# ZYNQ400-EMIO.net
KiCad netlist of a schematic drawn in Altium Designer
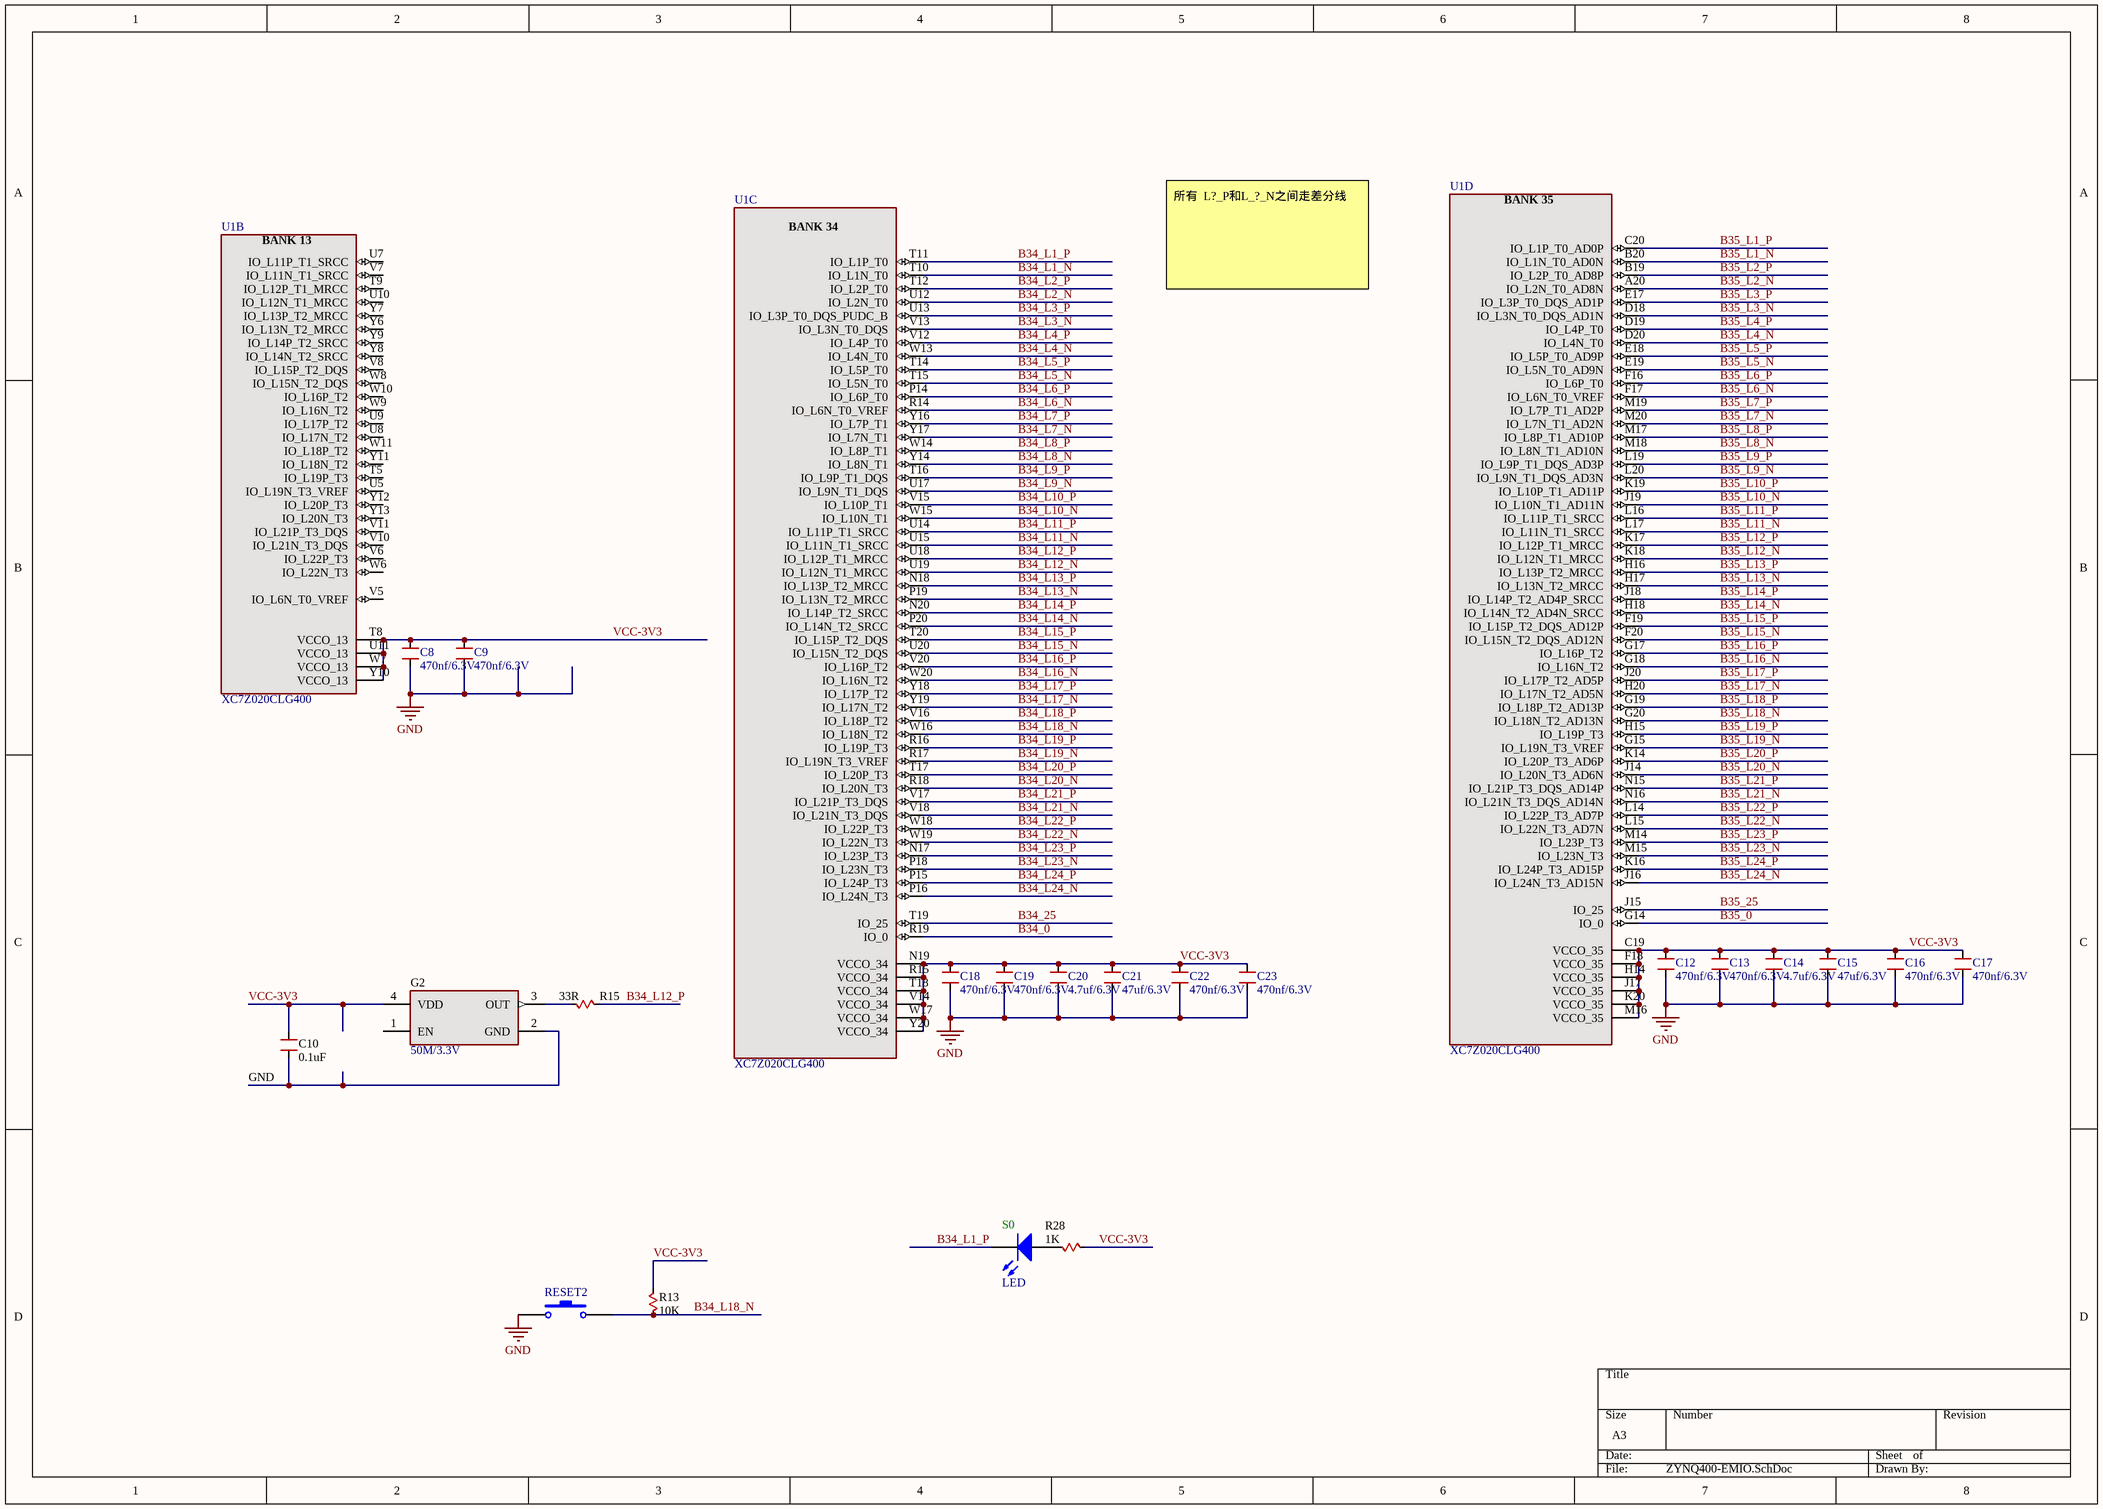
[diagram p0: ZYNQ400-EMIO.SchDoc]

(export (version "E")
  (design (tool "Eeschema 10.0.6"))
  (components
    (comp (ref "C8")
      (value "470nf/6.3V")
      (footprint "0402")
      (description "Generic Capacitor")
      (libsource (lib "Digilent") (part "CAPACITOR"))
    )
    (comp (ref "C9")
      (value "470nf/6.3V")
      (footprint "0402")
      (description "Generic Capacitor")
      (libsource (lib "Digilent") (part "CAPACITOR"))
    )
    (comp (ref "C10")
      (value "0.1uF")
      (footprint "0402")
      (description "Generic Capacitor")
      (fields (field (name "Comment") "0.1UF"))
      (libsource (lib "Digilent") (part "CAPACITOR"))
    )
    (comp (ref "C12")
      (value "470nf/6.3V")
      (footprint "0402")
      (description "Generic Capacitor")
      (libsource (lib "Digilent") (part "CAPACITOR"))
    )
    (comp (ref "C13")
      (value "470nf/6.3V")
      (footprint "0402")
      (description "Generic Capacitor")
      (libsource (lib "Digilent") (part "CAPACITOR"))
    )
    (comp (ref "C14")
      (value "4.7uf/6.3V")
      (footprint "0402")
      (description "Generic Capacitor")
      (libsource (lib "Digilent") (part "CAPACITOR"))
    )
    (comp (ref "C15")
      (value "47uf/6.3V")
      (footprint "0402")
      (description "Generic Capacitor")
      (libsource (lib "Digilent") (part "CAPACITOR"))
    )
    (comp (ref "C16")
      (value "470nf/6.3V")
      (footprint "0402")
      (description "Generic Capacitor")
      (libsource (lib "Digilent") (part "CAPACITOR"))
    )
    (comp (ref "C17")
      (value "470nf/6.3V")
      (footprint "0402")
      (description "Generic Capacitor")
      (libsource (lib "Digilent") (part "CAPACITOR"))
    )
    (comp (ref "C18")
      (value "470nf/6.3V")
      (footprint "0402")
      (description "Generic Capacitor")
      (libsource (lib "Digilent") (part "CAPACITOR"))
    )
    (comp (ref "C19")
      (value "470nf/6.3V")
      (footprint "0402")
      (description "Generic Capacitor")
      (libsource (lib "Digilent") (part "CAPACITOR"))
    )
    (comp (ref "C20")
      (value "4.7uf/6.3V")
      (footprint "0402")
      (description "Generic Capacitor")
      (libsource (lib "Digilent") (part "CAPACITOR"))
    )
    (comp (ref "C21")
      (value "47uf/6.3V")
      (footprint "0402")
      (description "Generic Capacitor")
      (libsource (lib "Digilent") (part "CAPACITOR"))
    )
    (comp (ref "C22")
      (value "470nf/6.3V")
      (footprint "0402")
      (description "Generic Capacitor")
      (libsource (lib "Digilent") (part "CAPACITOR"))
    )
    (comp (ref "C23")
      (value "470nf/6.3V")
      (footprint "0402")
      (description "Generic Capacitor")
      (libsource (lib "Digilent") (part "CAPACITOR"))
    )
    (comp (ref "G2")
      (value "50M/3.3V")
      (footprint "3.2*2.5")
      (description "3.3V HCMOS Oscillator")
      (fields (field (name "MANUFACTURER") "Fox Electronics"))
      (libsource (lib "Digilent") (part "FXO-HC5"))
    )
    (comp (ref "R13")
      (value "10K")
      (footprint "0402")
      (description "Generic Resistor")
      (libsource (lib "Digilent") (part "RESISTOR"))
    )
    (comp (ref "R15")
      (value "33R")
      (footprint "0402")
      (description "Generic Resistor")
      (libsource (lib "Digilent") (part "RESISTOR"))
    )
    (comp (ref "R28")
      (value "1K")
      (footprint "0402")
      (description "Generic Resistor")
      (libsource (lib "Digilent") (part "RESISTOR"))
    )
    (comp (ref "RESET2")
      (value "SW-PB")
      (footprint "micro button_2_SMD")
      (description "Switch")
      (fields (field (name "PUBLISHER") "Altium Limited"))
      (libsource (lib "M4(3333)") (part "SW-PB"))
    )
    (comp (ref "S0")
      (value "LED")
      (footprint "D0402")
      (description "Typical INFRARED GaAs LED")
      (fields (field (name "PUBLISHER") "Altium Limited"))
      (libsource (lib "Miscellaneous Devices") (part "LED0"))
    )
    (comp (ref "U1")
      (value "XC7Z020CLG400")
      (footprint "CLG400")
      (description "Zynq 7000 FPGA 20 Die, in a CSG 484 Package")
      (fields (field (name "MANUFACTURER") "Xilinx"))
      (libsource (lib "gjws") (part "XC7Z020-CLG400"))
    )
  )
  (nets
    (net (code "1") (name "/B34_0") (class "Default")
      (node (ref "U1") (pin "R19") (pinfunction "IO_0_R19") (pintype "bidirectional"))
    )
    (net (code "2") (name "/B34_25") (class "Default")
      (node (ref "U1") (pin "T19") (pinfunction "IO_25_T19") (pintype "bidirectional"))
    )
    (net (code "3") (name "/B34_L1_N") (class "Default")
      (node (ref "U1") (pin "T10") (pinfunction "IO_L1N_T0_T10") (pintype "bidirectional"))
    )
    (net (code "4") (name "/B34_L1_P") (class "Default")
      (node (ref "S0") (pin "2") (pinfunction "K_2") (pintype "passive"))
      (node (ref "U1") (pin "T11") (pinfunction "IO_L1P_T0_T11") (pintype "bidirectional"))
    )
    (net (code "5") (name "/B34_L2_N") (class "Default")
      (node (ref "U1") (pin "U12") (pinfunction "IO_L2N_T0_U12") (pintype "bidirectional"))
    )
    (net (code "6") (name "/B34_L2_P") (class "Default")
      (node (ref "U1") (pin "T12") (pinfunction "IO_L2P_T0_T12") (pintype "bidirectional"))
    )
    (net (code "7") (name "/B34_L3_N") (class "Default")
      (node (ref "U1") (pin "V13") (pinfunction "IO_L3N_T0_DQS_V13") (pintype "bidirectional"))
    )
    (net (code "8") (name "/B34_L3_P") (class "Default")
      (node (ref "U1") (pin "U13") (pinfunction "IO_L3P_T0_DQS_PUDC_B_U13") (pintype "bidirectional"))
    )
    (net (code "9") (name "/B34_L4_N") (class "Default")
      (node (ref "U1") (pin "W13") (pinfunction "IO_L4N_T0_W13") (pintype "bidirectional"))
    )
    (net (code "10") (name "/B34_L4_P") (class "Default")
      (node (ref "U1") (pin "V12") (pinfunction "IO_L4P_T0_V12") (pintype "bidirectional"))
    )
    (net (code "11") (name "/B34_L5_N") (class "Default")
      (node (ref "U1") (pin "T15") (pinfunction "IO_L5N_T0_T15") (pintype "bidirectional"))
    )
    (net (code "12") (name "/B34_L5_P") (class "Default")
      (node (ref "U1") (pin "T14") (pinfunction "IO_L5P_T0_T14") (pintype "bidirectional"))
    )
    (net (code "13") (name "/B34_L6_N") (class "Default")
      (node (ref "U1") (pin "R14") (pinfunction "IO_L6N_T0_VREF_R14") (pintype "bidirectional"))
    )
    (net (code "14") (name "/B34_L6_P") (class "Default")
      (node (ref "U1") (pin "P14") (pinfunction "IO_L6P_T0_P14") (pintype "bidirectional"))
    )
    (net (code "15") (name "/B34_L7_N") (class "Default")
      (node (ref "U1") (pin "Y17") (pinfunction "IO_L7N_T1_Y17") (pintype "bidirectional"))
    )
    (net (code "16") (name "/B34_L7_P") (class "Default")
      (node (ref "U1") (pin "Y16") (pinfunction "IO_L7P_T1_Y16") (pintype "bidirectional"))
    )
    (net (code "17") (name "/B34_L8_N") (class "Default")
      (node (ref "U1") (pin "Y14") (pinfunction "IO_L8N_T1_Y14") (pintype "bidirectional"))
    )
    (net (code "18") (name "/B34_L8_P") (class "Default")
      (node (ref "U1") (pin "W14") (pinfunction "IO_L8P_T1_W14") (pintype "bidirectional"))
    )
    (net (code "19") (name "/B34_L9_N") (class "Default")
      (node (ref "U1") (pin "U17") (pinfunction "IO_L9N_T1_DQS_U17") (pintype "bidirectional"))
    )
    (net (code "20") (name "/B34_L9_P") (class "Default")
      (node (ref "U1") (pin "T16") (pinfunction "IO_L9P_T1_DQS_T16") (pintype "bidirectional"))
    )
    (net (code "21") (name "/B34_L10_N") (class "Default")
      (node (ref "U1") (pin "W15") (pinfunction "IO_L10N_T1_W15") (pintype "bidirectional"))
    )
    (net (code "22") (name "/B34_L10_P") (class "Default")
      (node (ref "U1") (pin "V15") (pinfunction "IO_L10P_T1_V15") (pintype "bidirectional"))
    )
    (net (code "23") (name "/B34_L11_N") (class "Default")
      (node (ref "U1") (pin "U15") (pinfunction "IO_L11N_T1_SRCC_U15") (pintype "bidirectional"))
    )
    (net (code "24") (name "/B34_L11_P") (class "Default")
      (node (ref "U1") (pin "U14") (pinfunction "IO_L11P_T1_SRCC_U14") (pintype "bidirectional"))
    )
    (net (code "25") (name "/B34_L12_N") (class "Default")
      (node (ref "U1") (pin "U19") (pinfunction "IO_L12N_T1_MRCC_U19") (pintype "bidirectional"))
    )
    (net (code "26") (name "/B34_L12_P") (class "Default")
      (node (ref "R15") (pin "2") (pinfunction "2_2") (pintype "passive"))
      (node (ref "U1") (pin "U18") (pinfunction "IO_L12P_T1_MRCC_U18") (pintype "bidirectional"))
    )
    (net (code "27") (name "/B34_L13_N") (class "Default")
      (node (ref "U1") (pin "P19") (pinfunction "IO_L13N_T2_MRCC_P19") (pintype "bidirectional"))
    )
    (net (code "28") (name "/B34_L13_P") (class "Default")
      (node (ref "U1") (pin "N18") (pinfunction "IO_L13P_T2_MRCC_N18") (pintype "bidirectional"))
    )
    (net (code "29") (name "/B34_L14_N") (class "Default")
      (node (ref "U1") (pin "P20") (pinfunction "IO_L14N_T2_SRCC_P20") (pintype "bidirectional"))
    )
    (net (code "30") (name "/B34_L14_P") (class "Default")
      (node (ref "U1") (pin "N20") (pinfunction "IO_L14P_T2_SRCC_N20") (pintype "bidirectional"))
    )
    (net (code "31") (name "/B34_L15_N") (class "Default")
      (node (ref "U1") (pin "U20") (pinfunction "IO_L15N_T2_DQS_U20") (pintype "bidirectional"))
    )
    (net (code "32") (name "/B34_L15_P") (class "Default")
      (node (ref "U1") (pin "T20") (pinfunction "IO_L15P_T2_DQS_T20") (pintype "bidirectional"))
    )
    (net (code "33") (name "/B34_L16_N") (class "Default")
      (node (ref "U1") (pin "W20") (pinfunction "IO_L16N_T2_W20") (pintype "bidirectional"))
    )
    (net (code "34") (name "/B34_L16_P") (class "Default")
      (node (ref "U1") (pin "V20") (pinfunction "IO_L16P_T2_V20") (pintype "bidirectional"))
    )
    (net (code "35") (name "/B34_L17_N") (class "Default")
      (node (ref "U1") (pin "Y19") (pinfunction "IO_L17N_T2_Y19") (pintype "bidirectional"))
    )
    (net (code "36") (name "/B34_L17_P") (class "Default")
      (node (ref "U1") (pin "Y18") (pinfunction "IO_L17P_T2_Y18") (pintype "bidirectional"))
    )
    (net (code "37") (name "/B34_L18_N") (class "Default")
      (node (ref "R13") (pin "1") (pinfunction "1_1") (pintype "passive"))
      (node (ref "RESET2") (pin "2") (pinfunction "2_2") (pintype "passive"))
      (node (ref "U1") (pin "W16") (pinfunction "IO_L18N_T2_W16") (pintype "bidirectional"))
    )
    (net (code "38") (name "/B34_L18_P") (class "Default")
      (node (ref "U1") (pin "V16") (pinfunction "IO_L18P_T2_V16") (pintype "bidirectional"))
    )
    (net (code "39") (name "/B34_L19_N") (class "Default")
      (node (ref "U1") (pin "R17") (pinfunction "IO_L19N_T3_VREF_R17") (pintype "bidirectional"))
    )
    (net (code "40") (name "/B34_L19_P") (class "Default")
      (node (ref "U1") (pin "R16") (pinfunction "IO_L19P_T3_R16") (pintype "bidirectional"))
    )
    (net (code "41") (name "/B34_L20_N") (class "Default")
      (node (ref "U1") (pin "R18") (pinfunction "IO_L20N_T3_R18") (pintype "bidirectional"))
    )
    (net (code "42") (name "/B34_L20_P") (class "Default")
      (node (ref "U1") (pin "T17") (pinfunction "IO_L20P_T3_T17") (pintype "bidirectional"))
    )
    (net (code "43") (name "/B34_L21_N") (class "Default")
      (node (ref "U1") (pin "V18") (pinfunction "IO_L21N_T3_DQS_V18") (pintype "bidirectional"))
    )
    (net (code "44") (name "/B34_L21_P") (class "Default")
      (node (ref "U1") (pin "V17") (pinfunction "IO_L21P_T3_DQS_V17") (pintype "bidirectional"))
    )
    (net (code "45") (name "/B34_L22_N") (class "Default")
      (node (ref "U1") (pin "W19") (pinfunction "IO_L22N_T3_W19") (pintype "bidirectional"))
    )
    (net (code "46") (name "/B34_L22_P") (class "Default")
      (node (ref "U1") (pin "W18") (pinfunction "IO_L22P_T3_W18") (pintype "bidirectional"))
    )
    (net (code "47") (name "/B34_L23_N") (class "Default")
      (node (ref "U1") (pin "P18") (pinfunction "IO_L23N_T3_P18") (pintype "bidirectional"))
    )
    (net (code "48") (name "/B34_L23_P") (class "Default")
      (node (ref "U1") (pin "N17") (pinfunction "IO_L23P_T3_N17") (pintype "bidirectional"))
    )
    (net (code "49") (name "/B34_L24_N") (class "Default")
      (node (ref "U1") (pin "P16") (pinfunction "IO_L24N_T3_P16") (pintype "bidirectional"))
    )
    (net (code "50") (name "/B34_L24_P") (class "Default")
      (node (ref "U1") (pin "P15") (pinfunction "IO_L24P_T3_P15") (pintype "bidirectional"))
    )
    (net (code "51") (name "/B35_0") (class "Default")
      (node (ref "U1") (pin "G14") (pinfunction "IO_0_G14") (pintype "bidirectional"))
    )
    (net (code "52") (name "/B35_25") (class "Default")
      (node (ref "U1") (pin "J15") (pinfunction "IO_25_J15") (pintype "bidirectional"))
    )
    (net (code "53") (name "/B35_L1_N") (class "Default")
      (node (ref "U1") (pin "B20") (pinfunction "IO_L1N_T0_AD0N_B20") (pintype "bidirectional"))
    )
    (net (code "54") (name "/B35_L1_P") (class "Default")
      (node (ref "U1") (pin "C20") (pinfunction "IO_L1P_T0_AD0P_C20") (pintype "bidirectional"))
    )
    (net (code "55") (name "/B35_L2_N") (class "Default")
      (node (ref "U1") (pin "A20") (pinfunction "IO_L2N_T0_AD8N_A20") (pintype "bidirectional"))
    )
    (net (code "56") (name "/B35_L2_P") (class "Default")
      (node (ref "U1") (pin "B19") (pinfunction "IO_L2P_T0_AD8P_B19") (pintype "bidirectional"))
    )
    (net (code "57") (name "/B35_L3_N") (class "Default")
      (node (ref "U1") (pin "D18") (pinfunction "IO_L3N_T0_DQS_AD1N_D18") (pintype "bidirectional"))
    )
    (net (code "58") (name "/B35_L3_P") (class "Default")
      (node (ref "U1") (pin "E17") (pinfunction "IO_L3P_T0_DQS_AD1P_E17") (pintype "bidirectional"))
    )
    (net (code "59") (name "/B35_L4_N") (class "Default")
      (node (ref "U1") (pin "D20") (pinfunction "IO_L4N_T0_D20") (pintype "bidirectional"))
    )
    (net (code "60") (name "/B35_L4_P") (class "Default")
      (node (ref "U1") (pin "D19") (pinfunction "IO_L4P_T0_D19") (pintype "bidirectional"))
    )
    (net (code "61") (name "/B35_L5_N") (class "Default")
      (node (ref "U1") (pin "E19") (pinfunction "IO_L5N_T0_AD9N_E19") (pintype "bidirectional"))
    )
    (net (code "62") (name "/B35_L5_P") (class "Default")
      (node (ref "U1") (pin "E18") (pinfunction "IO_L5P_T0_AD9P_E18") (pintype "bidirectional"))
    )
    (net (code "63") (name "/B35_L6_N") (class "Default")
      (node (ref "U1") (pin "F17") (pinfunction "IO_L6N_T0_VREF_F17") (pintype "bidirectional"))
    )
    (net (code "64") (name "/B35_L6_P") (class "Default")
      (node (ref "U1") (pin "F16") (pinfunction "IO_L6P_T0_F16") (pintype "bidirectional"))
    )
    (net (code "65") (name "/B35_L7_N") (class "Default")
      (node (ref "U1") (pin "M20") (pinfunction "IO_L7N_T1_AD2N_M20") (pintype "bidirectional"))
    )
    (net (code "66") (name "/B35_L7_P") (class "Default")
      (node (ref "U1") (pin "M19") (pinfunction "IO_L7P_T1_AD2P_M19") (pintype "bidirectional"))
    )
    (net (code "67") (name "/B35_L8_N") (class "Default")
      (node (ref "U1") (pin "M18") (pinfunction "IO_L8N_T1_AD10N_M18") (pintype "bidirectional"))
    )
    (net (code "68") (name "/B35_L8_P") (class "Default")
      (node (ref "U1") (pin "M17") (pinfunction "IO_L8P_T1_AD10P_M17") (pintype "bidirectional"))
    )
    (net (code "69") (name "/B35_L9_N") (class "Default")
      (node (ref "U1") (pin "L20") (pinfunction "IO_L9N_T1_DQS_AD3N_L20") (pintype "bidirectional"))
    )
    (net (code "70") (name "/B35_L9_P") (class "Default")
      (node (ref "U1") (pin "L19") (pinfunction "IO_L9P_T1_DQS_AD3P_L19") (pintype "bidirectional"))
    )
    (net (code "71") (name "/B35_L10_N") (class "Default")
      (node (ref "U1") (pin "J19") (pinfunction "IO_L10N_T1_AD11N_J19") (pintype "bidirectional"))
    )
    (net (code "72") (name "/B35_L10_P") (class "Default")
      (node (ref "U1") (pin "K19") (pinfunction "IO_L10P_T1_AD11P_K19") (pintype "bidirectional"))
    )
    (net (code "73") (name "/B35_L11_N") (class "Default")
      (node (ref "U1") (pin "L17") (pinfunction "IO_L11N_T1_SRCC_L17") (pintype "bidirectional"))
    )
    (net (code "74") (name "/B35_L11_P") (class "Default")
      (node (ref "U1") (pin "L16") (pinfunction "IO_L11P_T1_SRCC_L16") (pintype "bidirectional"))
    )
    (net (code "75") (name "/B35_L12_N") (class "Default")
      (node (ref "U1") (pin "K18") (pinfunction "IO_L12N_T1_MRCC_K18") (pintype "bidirectional"))
    )
    (net (code "76") (name "/B35_L12_P") (class "Default")
      (node (ref "U1") (pin "K17") (pinfunction "IO_L12P_T1_MRCC_K17") (pintype "bidirectional"))
    )
    (net (code "77") (name "/B35_L13_N") (class "Default")
      (node (ref "U1") (pin "H17") (pinfunction "IO_L13N_T2_MRCC_H17") (pintype "bidirectional"))
    )
    (net (code "78") (name "/B35_L13_P") (class "Default")
      (node (ref "U1") (pin "H16") (pinfunction "IO_L13P_T2_MRCC_H16") (pintype "bidirectional"))
    )
    (net (code "79") (name "/B35_L14_N") (class "Default")
      (node (ref "U1") (pin "H18") (pinfunction "IO_L14N_T2_AD4N_SRCC_H18") (pintype "bidirectional"))
    )
    (net (code "80") (name "/B35_L14_P") (class "Default")
      (node (ref "U1") (pin "J18") (pinfunction "IO_L14P_T2_AD4P_SRCC_J18") (pintype "bidirectional"))
    )
    (net (code "81") (name "/B35_L15_N") (class "Default")
      (node (ref "U1") (pin "F20") (pinfunction "IO_L15N_T2_DQS_AD12N_F20") (pintype "bidirectional"))
    )
    (net (code "82") (name "/B35_L15_P") (class "Default")
      (node (ref "U1") (pin "F19") (pinfunction "IO_L15P_T2_DQS_AD12P_F19") (pintype "bidirectional"))
    )
    (net (code "83") (name "/B35_L16_N") (class "Default")
      (node (ref "U1") (pin "G18") (pinfunction "IO_L16N_T2_G18") (pintype "bidirectional"))
    )
    (net (code "84") (name "/B35_L16_P") (class "Default")
      (node (ref "U1") (pin "G17") (pinfunction "IO_L16P_T2_G17") (pintype "bidirectional"))
    )
    (net (code "85") (name "/B35_L17_N") (class "Default")
      (node (ref "U1") (pin "H20") (pinfunction "IO_L17N_T2_AD5N_H20") (pintype "bidirectional"))
    )
    (net (code "86") (name "/B35_L17_P") (class "Default")
      (node (ref "U1") (pin "J20") (pinfunction "IO_L17P_T2_AD5P_J20") (pintype "bidirectional"))
    )
    (net (code "87") (name "/B35_L18_N") (class "Default")
      (node (ref "U1") (pin "G20") (pinfunction "IO_L18N_T2_AD13N_G20") (pintype "bidirectional"))
    )
    (net (code "88") (name "/B35_L18_P") (class "Default")
      (node (ref "U1") (pin "G19") (pinfunction "IO_L18P_T2_AD13P_G19") (pintype "bidirectional"))
    )
    (net (code "89") (name "/B35_L19_N") (class "Default")
      (node (ref "U1") (pin "G15") (pinfunction "IO_L19N_T3_VREF_G15") (pintype "bidirectional"))
    )
    (net (code "90") (name "/B35_L19_P") (class "Default")
      (node (ref "U1") (pin "H15") (pinfunction "IO_L19P_T3_H15") (pintype "bidirectional"))
    )
    (net (code "91") (name "/B35_L20_N") (class "Default")
      (node (ref "U1") (pin "J14") (pinfunction "IO_L20N_T3_AD6N_J14") (pintype "bidirectional"))
    )
    (net (code "92") (name "/B35_L20_P") (class "Default")
      (node (ref "U1") (pin "K14") (pinfunction "IO_L20P_T3_AD6P_K14") (pintype "bidirectional"))
    )
    (net (code "93") (name "/B35_L21_N") (class "Default")
      (node (ref "U1") (pin "N16") (pinfunction "IO_L21N_T3_DQS_AD14N_N16") (pintype "bidirectional"))
    )
    (net (code "94") (name "/B35_L21_P") (class "Default")
      (node (ref "U1") (pin "N15") (pinfunction "IO_L21P_T3_DQS_AD14P_N15") (pintype "bidirectional"))
    )
    (net (code "95") (name "/B35_L22_N") (class "Default")
      (node (ref "U1") (pin "L15") (pinfunction "IO_L22N_T3_AD7N_L15") (pintype "bidirectional"))
    )
    (net (code "96") (name "/B35_L22_P") (class "Default")
      (node (ref "U1") (pin "L14") (pinfunction "IO_L22P_T3_AD7P_L14") (pintype "bidirectional"))
    )
    (net (code "97") (name "/B35_L23_N") (class "Default")
      (node (ref "U1") (pin "M15") (pinfunction "IO_L23N_T3_M15") (pintype "bidirectional"))
    )
    (net (code "98") (name "/B35_L23_P") (class "Default")
      (node (ref "U1") (pin "M14") (pinfunction "IO_L23P_T3_M14") (pintype "bidirectional"))
    )
    (net (code "99") (name "/B35_L24_N") (class "Default")
      (node (ref "U1") (pin "J16") (pinfunction "IO_L24N_T3_AD15N_J16") (pintype "bidirectional"))
    )
    (net (code "100") (name "/B35_L24_P") (class "Default")
      (node (ref "U1") (pin "K16") (pinfunction "IO_L24P_T3_AD15P_K16") (pintype "bidirectional"))
    )
    (net (code "101") (name "/VCC-3V3") (class "Default")
      (node (ref "C10") (pin "1") (pinfunction "1_1") (pintype "passive"))
      (node (ref "C12") (pin "1") (pinfunction "1_1") (pintype "passive"))
      (node (ref "C13") (pin "1") (pinfunction "1_1") (pintype "passive"))
      (node (ref "C14") (pin "1") (pinfunction "1_1") (pintype "passive"))
      (node (ref "C15") (pin "1") (pinfunction "1_1") (pintype "passive"))
      (node (ref "C16") (pin "1") (pinfunction "1_1") (pintype "passive"))
      (node (ref "C17") (pin "1") (pinfunction "1_1") (pintype "passive"))
      (node (ref "C18") (pin "1") (pinfunction "1_1") (pintype "passive"))
      (node (ref "C19") (pin "1") (pinfunction "1_1") (pintype "passive"))
      (node (ref "C20") (pin "1") (pinfunction "1_1") (pintype "passive"))
      (node (ref "C21") (pin "1") (pinfunction "1_1") (pintype "passive"))
      (node (ref "C22") (pin "1") (pinfunction "1_1") (pintype "passive"))
      (node (ref "C23") (pin "1") (pinfunction "1_1") (pintype "passive"))
      (node (ref "C8") (pin "1") (pinfunction "1_1") (pintype "passive"))
      (node (ref "C9") (pin "1") (pinfunction "1_1") (pintype "passive"))
      (node (ref "G2") (pin "4") (pinfunction "VDD_4") (pintype "power_in"))
      (node (ref "R13") (pin "2") (pinfunction "2_2") (pintype "passive"))
      (node (ref "R28") (pin "2") (pinfunction "2_2") (pintype "passive"))
      (node (ref "U1") (pin "C19") (pinfunction "VCCO_35_C19") (pintype "power_in"))
      (node (ref "U1") (pin "F18") (pinfunction "VCCO_35_F18") (pintype "power_in"))
      (node (ref "U1") (pin "H14") (pinfunction "VCCO_35_H14") (pintype "power_in"))
      (node (ref "U1") (pin "J17") (pinfunction "VCCO_35_J17") (pintype "power_in"))
      (node (ref "U1") (pin "K20") (pinfunction "VCCO_35_K20") (pintype "power_in"))
      (node (ref "U1") (pin "M16") (pinfunction "VCCO_35_M16") (pintype "power_in"))
      (node (ref "U1") (pin "N19") (pinfunction "VCCO_34_N19") (pintype "power_in"))
      (node (ref "U1") (pin "R15") (pinfunction "VCCO_34_R15") (pintype "power_in"))
      (node (ref "U1") (pin "T18") (pinfunction "VCCO_34_T18") (pintype "power_in"))
      (node (ref "U1") (pin "T8") (pinfunction "VCCO_13_T8") (pintype "power_in"))
      (node (ref "U1") (pin "U11") (pinfunction "VCCO_13_U11") (pintype "power_in"))
      (node (ref "U1") (pin "V14") (pinfunction "VCCO_34_V14") (pintype "power_in"))
      (node (ref "U1") (pin "W17") (pinfunction "VCCO_34_W17") (pintype "power_in"))
      (node (ref "U1") (pin "W7") (pinfunction "VCCO_13_W7") (pintype "power_in"))
      (node (ref "U1") (pin "Y10") (pinfunction "VCCO_13_Y10") (pintype "power_in"))
      (node (ref "U1") (pin "Y20") (pinfunction "VCCO_34_Y20") (pintype "power_in"))
    )
    (net (code "102") (name "GND") (class "Default")
      (node (ref "C10") (pin "2") (pinfunction "2_2") (pintype "passive"))
      (node (ref "C12") (pin "2") (pinfunction "2_2") (pintype "passive"))
      (node (ref "C13") (pin "2") (pinfunction "2_2") (pintype "passive"))
      (node (ref "C14") (pin "2") (pinfunction "2_2") (pintype "passive"))
      (node (ref "C15") (pin "2") (pinfunction "2_2") (pintype "passive"))
      (node (ref "C16") (pin "2") (pinfunction "2_2") (pintype "passive"))
      (node (ref "C17") (pin "2") (pinfunction "2_2") (pintype "passive"))
      (node (ref "C18") (pin "2") (pinfunction "2_2") (pintype "passive"))
      (node (ref "C19") (pin "2") (pinfunction "2_2") (pintype "passive"))
      (node (ref "C20") (pin "2") (pinfunction "2_2") (pintype "passive"))
      (node (ref "C21") (pin "2") (pinfunction "2_2") (pintype "passive"))
      (node (ref "C22") (pin "2") (pinfunction "2_2") (pintype "passive"))
      (node (ref "C23") (pin "2") (pinfunction "2_2") (pintype "passive"))
      (node (ref "C8") (pin "2") (pinfunction "2_2") (pintype "passive"))
      (node (ref "C9") (pin "2") (pinfunction "2_2") (pintype "passive"))
      (node (ref "G2") (pin "2") (pinfunction "GND_2") (pintype "power_in"))
      (node (ref "RESET2") (pin "1") (pinfunction "1_1") (pintype "passive"))
    )
    (net (code "103") (name "Net-(G2-OUT)") (class "Default")
      (node (ref "G2") (pin "3") (pinfunction "OUT_3") (pintype "output"))
      (node (ref "R15") (pin "1") (pinfunction "1_1") (pintype "passive"))
    )
    (net (code "104") (name "Net-(S0-A)") (class "Default")
      (node (ref "R28") (pin "1") (pinfunction "1_1") (pintype "passive"))
      (node (ref "S0") (pin "1") (pinfunction "A_1") (pintype "passive"))
    )
    (net (code "105") (name "unconnected-(G2-EN-Pad1)") (class "Default")
      (node (ref "G2") (pin "1") (pinfunction "EN_1") (pintype "passive"))
    )
    (net (code "106") (name "unconnected-(U1B-IO_L6N_T0_VREF-PadV5)") (class "Default")
      (node (ref "U1") (pin "V5") (pinfunction "IO_L6N_T0_VREF_V5") (pintype "bidirectional"))
    )
    (net (code "107") (name "unconnected-(U1B-IO_L11N_T1_SRCC-PadV7)") (class "Default")
      (node (ref "U1") (pin "V7") (pinfunction "IO_L11N_T1_SRCC_V7") (pintype "bidirectional"))
    )
    (net (code "108") (name "unconnected-(U1B-IO_L11P_T1_SRCC-PadU7)") (class "Default")
      (node (ref "U1") (pin "U7") (pinfunction "IO_L11P_T1_SRCC_U7") (pintype "bidirectional"))
    )
    (net (code "109") (name "unconnected-(U1B-IO_L12N_T1_MRCC-PadU10)") (class "Default")
      (node (ref "U1") (pin "U10") (pinfunction "IO_L12N_T1_MRCC_U10") (pintype "bidirectional"))
    )
    (net (code "110") (name "unconnected-(U1B-IO_L12P_T1_MRCC-PadT9)") (class "Default")
      (node (ref "U1") (pin "T9") (pinfunction "IO_L12P_T1_MRCC_T9") (pintype "bidirectional"))
    )
    (net (code "111") (name "unconnected-(U1B-IO_L13N_T2_MRCC-PadY6)") (class "Default")
      (node (ref "U1") (pin "Y6") (pinfunction "IO_L13N_T2_MRCC_Y6") (pintype "bidirectional"))
    )
    (net (code "112") (name "unconnected-(U1B-IO_L13P_T2_MRCC-PadY7)") (class "Default")
      (node (ref "U1") (pin "Y7") (pinfunction "IO_L13P_T2_MRCC_Y7") (pintype "bidirectional"))
    )
    (net (code "113") (name "unconnected-(U1B-IO_L14N_T2_SRCC-PadY8)") (class "Default")
      (node (ref "U1") (pin "Y8") (pinfunction "IO_L14N_T2_SRCC_Y8") (pintype "bidirectional"))
    )
    (net (code "114") (name "unconnected-(U1B-IO_L14P_T2_SRCC-PadY9)") (class "Default")
      (node (ref "U1") (pin "Y9") (pinfunction "IO_L14P_T2_SRCC_Y9") (pintype "bidirectional"))
    )
    (net (code "115") (name "unconnected-(U1B-IO_L15N_T2_DQS-PadW8)") (class "Default")
      (node (ref "U1") (pin "W8") (pinfunction "IO_L15N_T2_DQS_W8") (pintype "bidirectional"))
    )
    (net (code "116") (name "unconnected-(U1B-IO_L15P_T2_DQS-PadV8)") (class "Default")
      (node (ref "U1") (pin "V8") (pinfunction "IO_L15P_T2_DQS_V8") (pintype "bidirectional"))
    )
    (net (code "117") (name "unconnected-(U1B-IO_L16N_T2-PadW9)") (class "Default")
      (node (ref "U1") (pin "W9") (pinfunction "IO_L16N_T2_W9") (pintype "bidirectional"))
    )
    (net (code "118") (name "unconnected-(U1B-IO_L16P_T2-PadW10)") (class "Default")
      (node (ref "U1") (pin "W10") (pinfunction "IO_L16P_T2_W10") (pintype "bidirectional"))
    )
    (net (code "119") (name "unconnected-(U1B-IO_L17N_T2-PadU8)") (class "Default")
      (node (ref "U1") (pin "U8") (pinfunction "IO_L17N_T2_U8") (pintype "bidirectional"))
    )
    (net (code "120") (name "unconnected-(U1B-IO_L17P_T2-PadU9)") (class "Default")
      (node (ref "U1") (pin "U9") (pinfunction "IO_L17P_T2_U9") (pintype "bidirectional"))
    )
    (net (code "121") (name "unconnected-(U1B-IO_L18N_T2-PadY11)") (class "Default")
      (node (ref "U1") (pin "Y11") (pinfunction "IO_L18N_T2_Y11") (pintype "bidirectional"))
    )
    (net (code "122") (name "unconnected-(U1B-IO_L18P_T2-PadW11)") (class "Default")
      (node (ref "U1") (pin "W11") (pinfunction "IO_L18P_T2_W11") (pintype "bidirectional"))
    )
    (net (code "123") (name "unconnected-(U1B-IO_L19N_T3_VREF-PadU5)") (class "Default")
      (node (ref "U1") (pin "U5") (pinfunction "IO_L19N_T3_VREF_U5") (pintype "bidirectional"))
    )
    (net (code "124") (name "unconnected-(U1B-IO_L19P_T3-PadT5)") (class "Default")
      (node (ref "U1") (pin "T5") (pinfunction "IO_L19P_T3_T5") (pintype "bidirectional"))
    )
    (net (code "125") (name "unconnected-(U1B-IO_L20N_T3-PadY13)") (class "Default")
      (node (ref "U1") (pin "Y13") (pinfunction "IO_L20N_T3_Y13") (pintype "bidirectional"))
    )
    (net (code "126") (name "unconnected-(U1B-IO_L20P_T3-PadY12)") (class "Default")
      (node (ref "U1") (pin "Y12") (pinfunction "IO_L20P_T3_Y12") (pintype "bidirectional"))
    )
    (net (code "127") (name "unconnected-(U1B-IO_L21N_T3_DQS-PadV10)") (class "Default")
      (node (ref "U1") (pin "V10") (pinfunction "IO_L21N_T3_DQS_V10") (pintype "bidirectional"))
    )
    (net (code "128") (name "unconnected-(U1B-IO_L21P_T3_DQS-PadV11)") (class "Default")
      (node (ref "U1") (pin "V11") (pinfunction "IO_L21P_T3_DQS_V11") (pintype "bidirectional"))
    )
    (net (code "129") (name "unconnected-(U1B-IO_L22N_T3-PadW6)") (class "Default")
      (node (ref "U1") (pin "W6") (pinfunction "IO_L22N_T3_W6") (pintype "bidirectional"))
    )
    (net (code "130") (name "unconnected-(U1B-IO_L22P_T3-PadV6)") (class "Default")
      (node (ref "U1") (pin "V6") (pinfunction "IO_L22P_T3_V6") (pintype "bidirectional"))
    )
  )
)
